# 1-Schematic_CessnaCitationX_Front.net
KiCad netlist of a schematic drawn in EasyEDA
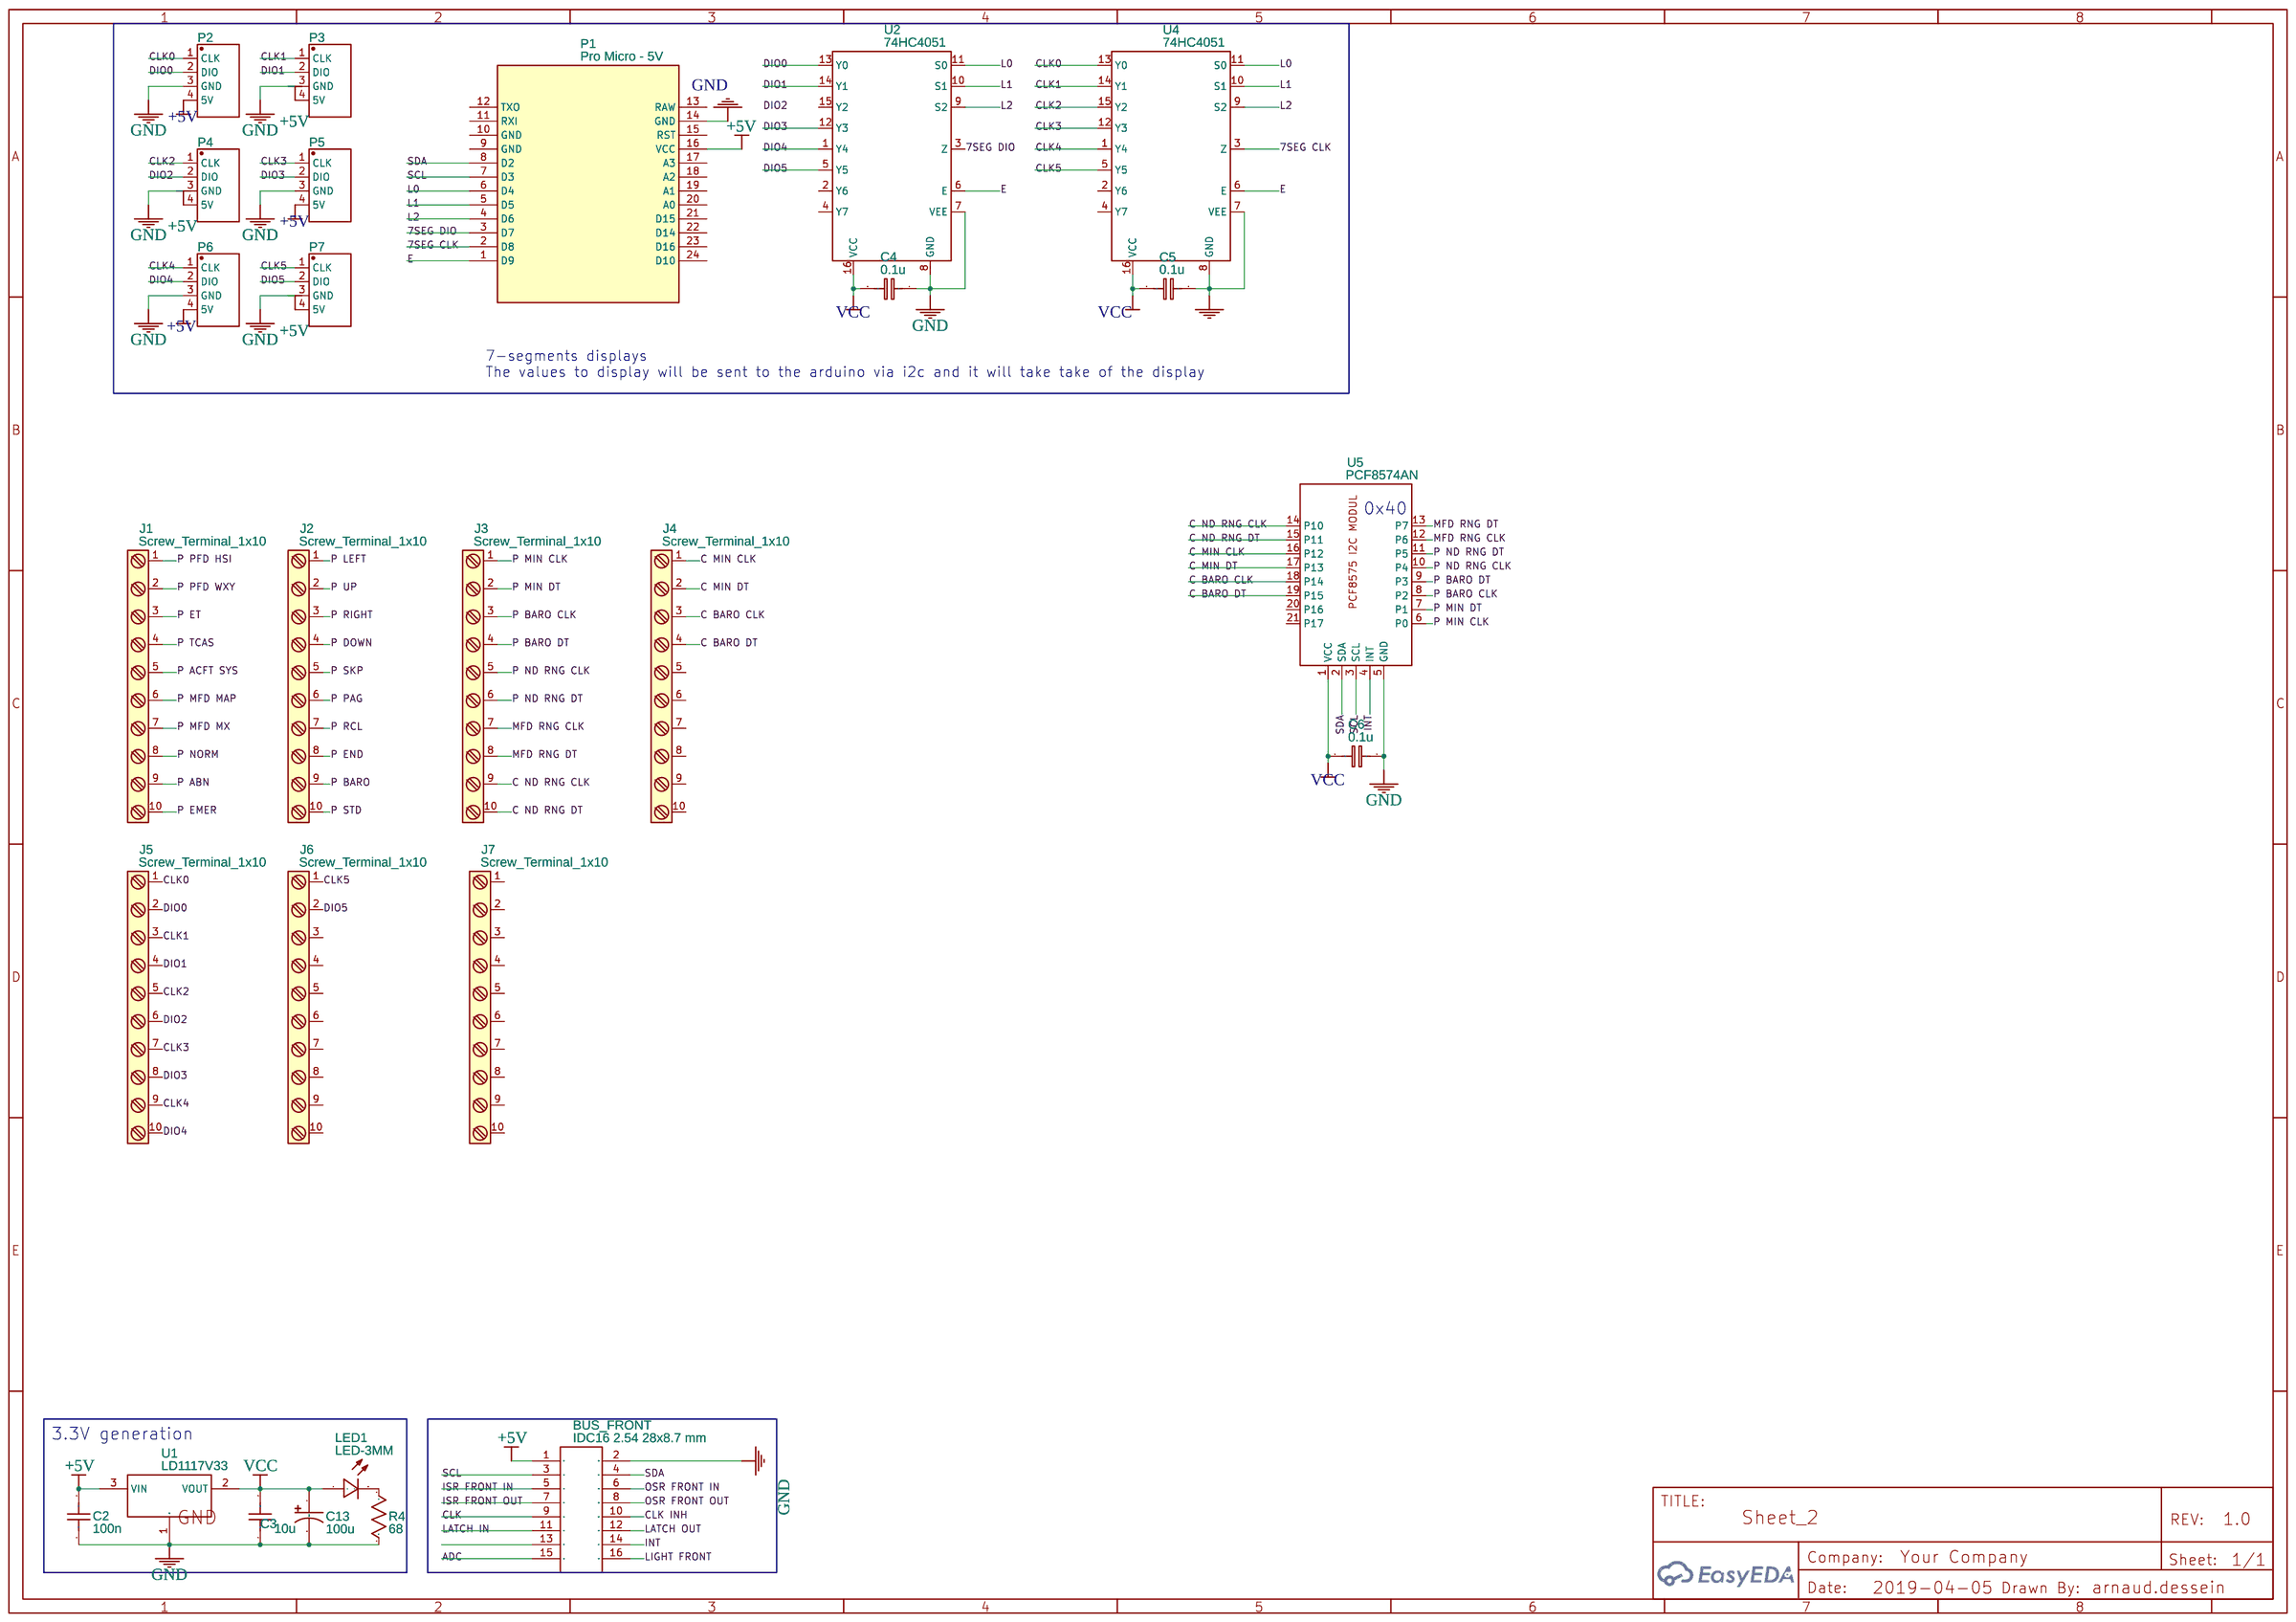
[diagram p0: schematic sheet]

(export (version "E")
  (design (tool "Eeschema 10.0.6"))
  (components
    (comp (ref "BUS_FRONT")
      (value "IDC16 2.54 28x8.7 mm")
      (fields (field (name "BOM_Manufacturer Part") "?"))
      (libsource (lib "") (part "Unknown_375_1120"))
    )
    (comp (ref "C2")
      (value "100n")
      (fields (field (name "BOM_Manufacturer Part") "?"))
      (libsource (lib "") (part "Cap_RAD-0.1_US"))
    )
    (comp (ref "C3")
      (value "10u")
      (fields (field (name "BOM_Manufacturer Part") "?"))
      (libsource (lib "") (part "Cap_RAD-0.1_US"))
    )
    (comp (ref "C4")
      (value "0.1u")
      (fields (field (name "BOM_Manufacturer Part") "?"))
      (libsource (lib "") (part "Cap_RAD-0.1_EU"))
    )
    (comp (ref "C5")
      (value "0.1u")
      (fields (field (name "BOM_Manufacturer Part") "?"))
      (libsource (lib "") (part "Cap_RAD-0.1_EU"))
    )
    (comp (ref "C6")
      (value "0.1u")
      (fields (field (name "BOM_Manufacturer Part") "?"))
      (libsource (lib "") (part "Cap_RAD-0.1_EU_1"))
    )
    (comp (ref "C13")
      (value "100u")
      (fields (field (name "BOM_Manufacturer Part") "?"))
      (libsource (lib "") (part "Cap_Electrolytic(TH)_D3.0XF1.5_US"))
    )
    (comp (ref "J1")
      (value "Screw_Terminal_1x10")
      (fields (field (name "BOM_Manufacturer Part") "?"))
      (libsource (lib "") (part "Unknown_100_395"))
    )
    (comp (ref "J2")
      (value "Screw_Terminal_1x10")
      (fields (field (name "BOM_Manufacturer Part") "?"))
      (libsource (lib "") (part "Unknown_215_395"))
    )
    (comp (ref "J3")
      (value "Screw_Terminal_1x10")
      (fields (field (name "BOM_Manufacturer Part") "?"))
      (libsource (lib "") (part "Unknown_340_395"))
    )
    (comp (ref "J4")
      (value "Screw_Terminal_1x10")
      (fields (field (name "BOM_Manufacturer Part") "?"))
      (libsource (lib "") (part "Unknown_475_395"))
    )
    (comp (ref "J5")
      (value "Screw_Terminal_1x10")
      (fields (field (name "BOM_Manufacturer Part") "?"))
      (libsource (lib "") (part "Unknown_100_625"))
    )
    (comp (ref "J6")
      (value "Screw_Terminal_1x10")
      (fields (field (name "BOM_Manufacturer Part") "?"))
      (libsource (lib "") (part "Unknown_215_625"))
    )
    (comp (ref "J7")
      (value "Screw_Terminal_1x10")
      (fields (field (name "BOM_Manufacturer Part") "?"))
      (libsource (lib "") (part "Unknown_345_625"))
    )
    (comp (ref "LED1")
      (value "LED-3MM")
      (fields
        (field (name "BOM_Manufacturer Part") "204-10SURD/S530-A3")
        (field (name "BOM_Supplier Part") "C99772")
      )
      (libsource (lib "") (part "Unknown_245_1055"))
    )
    (comp (ref "P1")
      (value "Pro Micro - 5V")
      (fields (field (name "BOM_Manufacturer Part") "?"))
      (libsource (lib "") (part "Unknown_415_125"))
    )
    (comp (ref "P2")
      (value "7seg display module TM1637")
      (fields
        (field (name "BOM_Manufacturer Part") "WJ2EDGVC-5.08-4P")
        (field (name "BOM_Supplier Part") "C8471")
      )
      (libsource (lib "") (part "Unknown_140_50"))
    )
    (comp (ref "P3")
      (value "7seg display module TM1637")
      (fields
        (field (name "BOM_Manufacturer Part") "WJ2EDGVC-5.08-4P")
        (field (name "BOM_Supplier Part") "C8471")
      )
      (libsource (lib "") (part "Unknown_220_50"))
    )
    (comp (ref "P4")
      (value "7seg display module TM1637")
      (fields
        (field (name "BOM_Manufacturer Part") "WJ2EDGVC-5.08-4P")
        (field (name "BOM_Supplier Part") "C8471")
      )
      (libsource (lib "") (part "Unknown_140_125"))
    )
    (comp (ref "P5")
      (value "7seg display module TM1637")
      (fields
        (field (name "BOM_Manufacturer Part") "WJ2EDGVC-5.08-4P")
        (field (name "BOM_Supplier Part") "C8471")
      )
      (libsource (lib "") (part "Unknown_220_125"))
    )
    (comp (ref "P6")
      (value "7seg display module TM1637")
      (fields
        (field (name "BOM_Manufacturer Part") "WJ2EDGVC-5.08-4P")
        (field (name "BOM_Supplier Part") "C8471")
      )
      (libsource (lib "") (part "Unknown_140_200"))
    )
    (comp (ref "P7")
      (value "7seg display module TM1637")
      (fields
        (field (name "BOM_Manufacturer Part") "WJ2EDGVC-5.08-4P")
        (field (name "BOM_Supplier Part") "C8471")
      )
      (libsource (lib "") (part "Unknown_220_200"))
    )
    (comp (ref "R4")
      (value "68")
      (fields (field (name "BOM_Manufacturer Part") "?"))
      (libsource (lib "") (part "Res_AXIAL-0.3(1/8W)_US"))
    )
    (comp (ref "U1")
      (value "LD1117V33")
      (fields (field (name "BOM_Supplier Part") "C283467"))
      (libsource (lib "") (part "Unknown_115_1080"))
    )
    (comp (ref "U2")
      (value "74HC4051")
      (fields (field (name "BOM_Manufacturer Part") "?"))
      (libsource (lib "") (part "Unknown_635_100"))
    )
    (comp (ref "U4")
      (value "74HC4051")
      (fields (field (name "BOM_Manufacturer Part") "?"))
      (libsource (lib "") (part "Unknown_835_100"))
    )
    (comp (ref "U5")
      (value "PCF8574AN")
      (fields (field (name "BOM_Manufacturer Part") "?"))
      (libsource (lib "") (part "Unknown_905_350"))
    )
  )
  (nets
    (net (code "1") (name "+5V") (class "Default")
      (node (ref "BUS_FRONT") (pin "1") (pinfunction "P1_1") (pintype "unspecified"))
      (node (ref "C2") (pin "2") (pinfunction "2_2") (pintype "unspecified"))
      (node (ref "P1") (pin "16") (pinfunction "VCC_16") (pintype "unspecified"))
      (node (ref "P2") (pin "4") (pinfunction "5V_4") (pintype "unspecified"))
      (node (ref "P3") (pin "4") (pinfunction "5V_4") (pintype "unspecified"))
      (node (ref "P4") (pin "4") (pinfunction "5V_4") (pintype "unspecified"))
      (node (ref "P5") (pin "4") (pinfunction "5V_4") (pintype "unspecified"))
      (node (ref "P6") (pin "4") (pinfunction "5V_4") (pintype "unspecified"))
      (node (ref "P7") (pin "4") (pinfunction "5V_4") (pintype "unspecified"))
      (node (ref "U1") (pin "3") (pinfunction "VIN_3") (pintype "passive"))
    )
    (net (code "2") (name "/7SEG CLK") (class "Default")
      (node (ref "P1") (pin "2") (pinfunction "D8_2") (pintype "unspecified"))
      (node (ref "U4") (pin "3") (pinfunction "Z_3") (pintype "unspecified"))
    )
    (net (code "3") (name "/7SEG DIO") (class "Default")
      (node (ref "P1") (pin "3") (pinfunction "D7_3") (pintype "unspecified"))
      (node (ref "U2") (pin "3") (pinfunction "Z_3") (pintype "unspecified"))
    )
    (net (code "4") (name "/ADC") (class "Default")
      (node (ref "BUS_FRONT") (pin "15") (pinfunction "15_15") (pintype "unspecified"))
    )
    (net (code "5") (name "/C BARO CLK") (class "Default")
      (node (ref "J4") (pin "3") (pintype "unspecified"))
      (node (ref "U5") (pin "18") (pinfunction "P14_18") (pintype "unspecified"))
    )
    (net (code "6") (name "/C BARO DT") (class "Default")
      (node (ref "J4") (pin "4") (pintype "unspecified"))
      (node (ref "U5") (pin "19") (pinfunction "P15_19") (pintype "unspecified"))
    )
    (net (code "7") (name "/C MIN CLK") (class "Default")
      (node (ref "J4") (pin "1") (pintype "unspecified"))
      (node (ref "U5") (pin "16") (pinfunction "P12_16") (pintype "unspecified"))
    )
    (net (code "8") (name "/C MIN DT") (class "Default")
      (node (ref "J4") (pin "2") (pintype "unspecified"))
      (node (ref "U5") (pin "17") (pinfunction "P13_17") (pintype "unspecified"))
    )
    (net (code "9") (name "/C ND RNG CLK") (class "Default")
      (node (ref "J3") (pin "9") (pintype "unspecified"))
      (node (ref "U5") (pin "14") (pinfunction "P10_14") (pintype "unspecified"))
    )
    (net (code "10") (name "/C ND RNG DT") (class "Default")
      (node (ref "J3") (pin "10") (pintype "unspecified"))
      (node (ref "U5") (pin "15") (pinfunction "P11_15") (pintype "unspecified"))
    )
    (net (code "11") (name "/CLK") (class "Default")
      (node (ref "BUS_FRONT") (pin "9") (pinfunction "P9_9") (pintype "unspecified"))
    )
    (net (code "12") (name "/CLK INH") (class "Default")
      (node (ref "BUS_FRONT") (pin "10") (pinfunction "P10_10") (pintype "unspecified"))
    )
    (net (code "13") (name "/CLK0") (class "Default")
      (node (ref "J5") (pin "1") (pintype "unspecified"))
      (node (ref "P2") (pin "1") (pinfunction "CLK_1") (pintype "unspecified"))
      (node (ref "U4") (pin "13") (pinfunction "Y0_13") (pintype "unspecified"))
    )
    (net (code "14") (name "/CLK1") (class "Default")
      (node (ref "J5") (pin "3") (pintype "unspecified"))
      (node (ref "P3") (pin "1") (pinfunction "CLK_1") (pintype "unspecified"))
      (node (ref "U4") (pin "14") (pinfunction "Y1_14") (pintype "unspecified"))
    )
    (net (code "15") (name "/CLK2") (class "Default")
      (node (ref "J5") (pin "5") (pintype "unspecified"))
      (node (ref "P4") (pin "1") (pinfunction "CLK_1") (pintype "unspecified"))
      (node (ref "U4") (pin "15") (pinfunction "Y2_15") (pintype "unspecified"))
    )
    (net (code "16") (name "/CLK3") (class "Default")
      (node (ref "J5") (pin "7") (pintype "unspecified"))
      (node (ref "P5") (pin "1") (pinfunction "CLK_1") (pintype "unspecified"))
      (node (ref "U4") (pin "12") (pinfunction "Y3_12") (pintype "unspecified"))
    )
    (net (code "17") (name "/CLK4") (class "Default")
      (node (ref "J5") (pin "9") (pintype "unspecified"))
      (node (ref "P6") (pin "1") (pinfunction "CLK_1") (pintype "unspecified"))
      (node (ref "U4") (pin "1") (pinfunction "Y4_1") (pintype "unspecified"))
    )
    (net (code "18") (name "/CLK5") (class "Default")
      (node (ref "J6") (pin "1") (pintype "unspecified"))
      (node (ref "P7") (pin "1") (pinfunction "CLK_1") (pintype "unspecified"))
      (node (ref "U4") (pin "5") (pinfunction "Y5_5") (pintype "unspecified"))
    )
    (net (code "19") (name "/DIO0") (class "Default")
      (node (ref "J5") (pin "2") (pintype "unspecified"))
      (node (ref "P2") (pin "2") (pinfunction "DIO_2") (pintype "unspecified"))
      (node (ref "U2") (pin "13") (pinfunction "Y0_13") (pintype "unspecified"))
    )
    (net (code "20") (name "/DIO1") (class "Default")
      (node (ref "J5") (pin "4") (pintype "unspecified"))
      (node (ref "P3") (pin "2") (pinfunction "DIO_2") (pintype "unspecified"))
      (node (ref "U2") (pin "14") (pinfunction "Y1_14") (pintype "unspecified"))
    )
    (net (code "21") (name "/DIO2") (class "Default")
      (node (ref "J5") (pin "6") (pintype "unspecified"))
      (node (ref "P4") (pin "2") (pinfunction "DIO_2") (pintype "unspecified"))
    )
    (net (code "22") (name "/DIO3") (class "Default")
      (node (ref "J5") (pin "8") (pintype "unspecified"))
      (node (ref "P5") (pin "2") (pinfunction "DIO_2") (pintype "unspecified"))
      (node (ref "U2") (pin "12") (pinfunction "Y3_12") (pintype "unspecified"))
    )
    (net (code "23") (name "/DIO4") (class "Default")
      (node (ref "J5") (pin "10") (pintype "unspecified"))
      (node (ref "P6") (pin "2") (pinfunction "DIO_2") (pintype "unspecified"))
      (node (ref "U2") (pin "1") (pinfunction "Y4_1") (pintype "unspecified"))
    )
    (net (code "24") (name "/DIO5") (class "Default")
      (node (ref "J6") (pin "2") (pintype "unspecified"))
      (node (ref "P7") (pin "2") (pinfunction "DIO_2") (pintype "unspecified"))
      (node (ref "U2") (pin "5") (pinfunction "Y5_5") (pintype "unspecified"))
    )
    (net (code "25") (name "/E") (class "Default")
      (node (ref "P1") (pin "1") (pinfunction "D9_1") (pintype "unspecified"))
      (node (ref "U2") (pin "6") (pinfunction "E_6") (pintype "unspecified"))
      (node (ref "U4") (pin "6") (pinfunction "E_6") (pintype "unspecified"))
    )
    (net (code "26") (name "/INT") (class "Default")
      (node (ref "BUS_FRONT") (pin "14") (pinfunction "14_14") (pintype "unspecified"))
      (node (ref "U5") (pin "4") (pinfunction "INT_4") (pintype "unspecified"))
    )
    (net (code "27") (name "/ISR FRONT IN") (class "Default")
      (node (ref "BUS_FRONT") (pin "5") (pinfunction "P5_5") (pintype "unspecified"))
    )
    (net (code "28") (name "/ISR FRONT OUT") (class "Default")
      (node (ref "BUS_FRONT") (pin "7") (pinfunction "P7_7") (pintype "unspecified"))
    )
    (net (code "29") (name "/L0") (class "Default")
      (node (ref "P1") (pin "6") (pinfunction "D4_6") (pintype "unspecified"))
      (node (ref "U2") (pin "11") (pinfunction "S0_11") (pintype "unspecified"))
      (node (ref "U4") (pin "11") (pinfunction "S0_11") (pintype "unspecified"))
    )
    (net (code "30") (name "/L1") (class "Default")
      (node (ref "P1") (pin "5") (pinfunction "D5_5") (pintype "unspecified"))
      (node (ref "U2") (pin "10") (pinfunction "S1_10") (pintype "unspecified"))
      (node (ref "U4") (pin "10") (pinfunction "S1_10") (pintype "unspecified"))
    )
    (net (code "31") (name "/L2") (class "Default")
      (node (ref "P1") (pin "4") (pinfunction "D6_4") (pintype "unspecified"))
      (node (ref "U2") (pin "9") (pinfunction "S2_9") (pintype "unspecified"))
      (node (ref "U4") (pin "9") (pinfunction "S2_9") (pintype "unspecified"))
    )
    (net (code "32") (name "/LATCH IN") (class "Default")
      (node (ref "BUS_FRONT") (pin "11") (pinfunction "11_11") (pintype "unspecified"))
    )
    (net (code "33") (name "/LATCH OUT") (class "Default")
      (node (ref "BUS_FRONT") (pin "12") (pinfunction "12_12") (pintype "unspecified"))
    )
    (net (code "34") (name "/LIGHT FRONT") (class "Default")
      (node (ref "BUS_FRONT") (pin "16") (pinfunction "16_16") (pintype "unspecified"))
    )
    (net (code "35") (name "/MFD RNG CLK") (class "Default")
      (node (ref "J3") (pin "7") (pintype "unspecified"))
      (node (ref "U5") (pin "12") (pinfunction "P6_12") (pintype "unspecified"))
    )
    (net (code "36") (name "/MFD RNG DT") (class "Default")
      (node (ref "J3") (pin "8") (pintype "unspecified"))
      (node (ref "U5") (pin "13") (pinfunction "P7_13") (pintype "unspecified"))
    )
    (net (code "37") (name "/OSR FRONT IN") (class "Default")
      (node (ref "BUS_FRONT") (pin "6") (pinfunction "P6_6") (pintype "unspecified"))
    )
    (net (code "38") (name "/OSR FRONT OUT") (class "Default")
      (node (ref "BUS_FRONT") (pin "8") (pinfunction "P8_8") (pintype "unspecified"))
    )
    (net (code "39") (name "/P ABN") (class "Default") (node (ref "J1") (pin "9") (pintype "unspecified")))
    (net (code "40") (name "/P ACFT SYS") (class "Default")
      (node (ref "J1") (pin "5") (pintype "unspecified"))
    )
    (net (code "41") (name "/P BARO") (class "Default") (node (ref "J2") (pin "9") (pintype "unspecified")))
    (net (code "42") (name "/P BARO CLK") (class "Default")
      (node (ref "J3") (pin "3") (pintype "unspecified"))
      (node (ref "U5") (pin "8") (pinfunction "P2_8") (pintype "unspecified"))
    )
    (net (code "43") (name "/P BARO DT") (class "Default")
      (node (ref "J3") (pin "4") (pintype "unspecified"))
      (node (ref "U5") (pin "9") (pinfunction "P3_9") (pintype "unspecified"))
    )
    (net (code "44") (name "/P DOWN") (class "Default") (node (ref "J2") (pin "4") (pintype "unspecified")))
    (net (code "45") (name "/P EMER") (class "Default") (node (ref "J1") (pin "10") (pintype "unspecified")))
    (net (code "46") (name "/P END") (class "Default") (node (ref "J2") (pin "8") (pintype "unspecified")))
    (net (code "47") (name "/P ET") (class "Default") (node (ref "J1") (pin "3") (pintype "unspecified")))
    (net (code "48") (name "/P LEFT") (class "Default") (node (ref "J2") (pin "1") (pintype "unspecified")))
    (net (code "49") (name "/P MFD MAP") (class "Default")
      (node (ref "J1") (pin "6") (pintype "unspecified"))
    )
    (net (code "50") (name "/P MFD MX") (class "Default") (node (ref "J1") (pin "7") (pintype "unspecified")))
    (net (code "51") (name "/P MIN CLK") (class "Default")
      (node (ref "J3") (pin "1") (pintype "unspecified"))
      (node (ref "U5") (pin "6") (pinfunction "P0_6") (pintype "unspecified"))
    )
    (net (code "52") (name "/P MIN DT") (class "Default")
      (node (ref "J3") (pin "2") (pintype "unspecified"))
      (node (ref "U5") (pin "7") (pinfunction "P1_7") (pintype "unspecified"))
    )
    (net (code "53") (name "/P ND RNG CLK") (class "Default")
      (node (ref "J3") (pin "5") (pintype "unspecified"))
      (node (ref "U5") (pin "10") (pinfunction "P4_10") (pintype "unspecified"))
    )
    (net (code "54") (name "/P ND RNG DT") (class "Default")
      (node (ref "J3") (pin "6") (pintype "unspecified"))
      (node (ref "U5") (pin "11") (pinfunction "P5_11") (pintype "unspecified"))
    )
    (net (code "55") (name "/P NORM") (class "Default") (node (ref "J1") (pin "8") (pintype "unspecified")))
    (net (code "56") (name "/P PAG") (class "Default") (node (ref "J2") (pin "6") (pintype "unspecified")))
    (net (code "57") (name "/P PFD HSI") (class "Default")
      (node (ref "J1") (pin "1") (pintype "unspecified"))
    )
    (net (code "58") (name "/P PFD WXY") (class "Default")
      (node (ref "J1") (pin "2") (pintype "unspecified"))
    )
    (net (code "59") (name "/P RCL") (class "Default") (node (ref "J2") (pin "7") (pintype "unspecified")))
    (net (code "60") (name "/P RIGHT") (class "Default") (node (ref "J2") (pin "3") (pintype "unspecified")))
    (net (code "61") (name "/P SKP") (class "Default") (node (ref "J2") (pin "5") (pintype "unspecified")))
    (net (code "62") (name "/P STD") (class "Default") (node (ref "J2") (pin "10") (pintype "unspecified")))
    (net (code "63") (name "/P TCAS") (class "Default") (node (ref "J1") (pin "4") (pintype "unspecified")))
    (net (code "64") (name "/P UP") (class "Default") (node (ref "J2") (pin "2") (pintype "unspecified")))
    (net (code "65") (name "/SCL") (class "Default")
      (node (ref "BUS_FRONT") (pin "3") (pinfunction "P3_3") (pintype "unspecified"))
      (node (ref "P1") (pin "7") (pinfunction "D3_7") (pintype "unspecified"))
      (node (ref "U5") (pin "3") (pinfunction "SCL_3") (pintype "unspecified"))
    )
    (net (code "66") (name "/SDA") (class "Default")
      (node (ref "BUS_FRONT") (pin "4") (pinfunction "P4_4") (pintype "unspecified"))
      (node (ref "P1") (pin "8") (pinfunction "D2_8") (pintype "unspecified"))
      (node (ref "U5") (pin "2") (pinfunction "SDA_2") (pintype "unspecified"))
    )
    (net (code "67") (name "GND") (class "Default")
      (node (ref "BUS_FRONT") (pin "2") (pinfunction "P2_2") (pintype "unspecified"))
      (node (ref "C13") (pin "2") (pinfunction "2_2") (pintype "unspecified"))
      (node (ref "C2") (pin "1") (pinfunction "1_1") (pintype "unspecified"))
      (node (ref "C3") (pin "1") (pinfunction "1_1") (pintype "unspecified"))
      (node (ref "C4") (pin "1") (pinfunction "1_1") (pintype "unspecified"))
      (node (ref "C5") (pin "1") (pinfunction "1_1") (pintype "unspecified"))
      (node (ref "C6") (pin "1") (pinfunction "1_1") (pintype "unspecified"))
      (node (ref "P1") (pin "14") (pinfunction "GND_14") (pintype "unspecified"))
      (node (ref "P2") (pin "3") (pinfunction "GND_3") (pintype "unspecified"))
      (node (ref "P3") (pin "3") (pinfunction "GND_3") (pintype "unspecified"))
      (node (ref "P4") (pin "3") (pinfunction "GND_3") (pintype "unspecified"))
      (node (ref "P5") (pin "3") (pinfunction "GND_3") (pintype "unspecified"))
      (node (ref "P6") (pin "3") (pinfunction "GND_3") (pintype "unspecified"))
      (node (ref "P7") (pin "3") (pinfunction "GND_3") (pintype "unspecified"))
      (node (ref "R4") (pin "2") (pinfunction "2_2") (pintype "unspecified"))
      (node (ref "U1") (pin "1") (pinfunction "GND_1") (pintype "unspecified"))
      (node (ref "U2") (pin "7") (pinfunction "VEE_7") (pintype "unspecified"))
      (node (ref "U2") (pin "8") (pinfunction "GND_8") (pintype "unspecified"))
      (node (ref "U4") (pin "7") (pinfunction "VEE_7") (pintype "unspecified"))
      (node (ref "U4") (pin "8") (pinfunction "GND_8") (pintype "unspecified"))
      (node (ref "U5") (pin "5") (pinfunction "GND_5") (pintype "unspecified"))
    )
    (net (code "68") (name "Net-(LED1--)") (class "Default")
      (node (ref "LED1") (pin "2") (pinfunction "-_2") (pintype "unspecified"))
      (node (ref "R4") (pin "1") (pinfunction "1_1") (pintype "unspecified"))
    )
    (net (code "69") (name "VCC") (class "Default")
      (node (ref "C13") (pin "1") (pinfunction "1_1") (pintype "unspecified"))
      (node (ref "C3") (pin "2") (pinfunction "2_2") (pintype "unspecified"))
      (node (ref "C4") (pin "2") (pinfunction "2_2") (pintype "unspecified"))
      (node (ref "C5") (pin "2") (pinfunction "2_2") (pintype "unspecified"))
      (node (ref "C6") (pin "2") (pinfunction "2_2") (pintype "unspecified"))
      (node (ref "LED1") (pin "1") (pinfunction "+_1") (pintype "unspecified"))
      (node (ref "U1") (pin "2") (pinfunction "VOUT_2") (pintype "passive"))
      (node (ref "U2") (pin "16") (pinfunction "VCC_16") (pintype "unspecified"))
      (node (ref "U4") (pin "16") (pinfunction "VCC_16") (pintype "unspecified"))
      (node (ref "U5") (pin "1") (pinfunction "VCC_1") (pintype "unspecified"))
    )
    (net (code "70") (name "unconnected-(BUS_FRONT-Pad13)") (class "Default")
      (node (ref "BUS_FRONT") (pin "13") (pinfunction "13_13") (pintype "unspecified"))
    )
    (net (code "71") (name "unconnected-(J4-Pad5)") (class "Default")
      (node (ref "J4") (pin "5") (pintype "unspecified"))
    )
    (net (code "72") (name "unconnected-(J4-Pad6)") (class "Default")
      (node (ref "J4") (pin "6") (pintype "unspecified"))
    )
    (net (code "73") (name "unconnected-(J4-Pad7)") (class "Default")
      (node (ref "J4") (pin "7") (pintype "unspecified"))
    )
    (net (code "74") (name "unconnected-(J4-Pad8)") (class "Default")
      (node (ref "J4") (pin "8") (pintype "unspecified"))
    )
    (net (code "75") (name "unconnected-(J4-Pad9)") (class "Default")
      (node (ref "J4") (pin "9") (pintype "unspecified"))
    )
    (net (code "76") (name "unconnected-(J4-Pad10)") (class "Default")
      (node (ref "J4") (pin "10") (pintype "unspecified"))
    )
    (net (code "77") (name "unconnected-(J6-Pad3)") (class "Default")
      (node (ref "J6") (pin "3") (pintype "unspecified"))
    )
    (net (code "78") (name "unconnected-(J6-Pad4)") (class "Default")
      (node (ref "J6") (pin "4") (pintype "unspecified"))
    )
    (net (code "79") (name "unconnected-(J6-Pad5)") (class "Default")
      (node (ref "J6") (pin "5") (pintype "unspecified"))
    )
    (net (code "80") (name "unconnected-(J6-Pad6)") (class "Default")
      (node (ref "J6") (pin "6") (pintype "unspecified"))
    )
    (net (code "81") (name "unconnected-(J6-Pad7)") (class "Default")
      (node (ref "J6") (pin "7") (pintype "unspecified"))
    )
    (net (code "82") (name "unconnected-(J6-Pad8)") (class "Default")
      (node (ref "J6") (pin "8") (pintype "unspecified"))
    )
    (net (code "83") (name "unconnected-(J6-Pad9)") (class "Default")
      (node (ref "J6") (pin "9") (pintype "unspecified"))
    )
    (net (code "84") (name "unconnected-(J6-Pad10)") (class "Default")
      (node (ref "J6") (pin "10") (pintype "unspecified"))
    )
    (net (code "85") (name "unconnected-(J7-Pad1)") (class "Default")
      (node (ref "J7") (pin "1") (pintype "unspecified"))
    )
    (net (code "86") (name "unconnected-(J7-Pad2)") (class "Default")
      (node (ref "J7") (pin "2") (pintype "unspecified"))
    )
    (net (code "87") (name "unconnected-(J7-Pad3)") (class "Default")
      (node (ref "J7") (pin "3") (pintype "unspecified"))
    )
    (net (code "88") (name "unconnected-(J7-Pad4)") (class "Default")
      (node (ref "J7") (pin "4") (pintype "unspecified"))
    )
    (net (code "89") (name "unconnected-(J7-Pad5)") (class "Default")
      (node (ref "J7") (pin "5") (pintype "unspecified"))
    )
    (net (code "90") (name "unconnected-(J7-Pad6)") (class "Default")
      (node (ref "J7") (pin "6") (pintype "unspecified"))
    )
    (net (code "91") (name "unconnected-(J7-Pad7)") (class "Default")
      (node (ref "J7") (pin "7") (pintype "unspecified"))
    )
    (net (code "92") (name "unconnected-(J7-Pad8)") (class "Default")
      (node (ref "J7") (pin "8") (pintype "unspecified"))
    )
    (net (code "93") (name "unconnected-(J7-Pad9)") (class "Default")
      (node (ref "J7") (pin "9") (pintype "unspecified"))
    )
    (net (code "94") (name "unconnected-(J7-Pad10)") (class "Default")
      (node (ref "J7") (pin "10") (pintype "unspecified"))
    )
    (net (code "95") (name "unconnected-(P1-A0-Pad20)") (class "Default")
      (node (ref "P1") (pin "20") (pinfunction "A0_20") (pintype "unspecified"))
    )
    (net (code "96") (name "unconnected-(P1-A1-Pad19)") (class "Default")
      (node (ref "P1") (pin "19") (pinfunction "A1_19") (pintype "unspecified"))
    )
    (net (code "97") (name "unconnected-(P1-A2-Pad18)") (class "Default")
      (node (ref "P1") (pin "18") (pinfunction "A2_18") (pintype "unspecified"))
    )
    (net (code "98") (name "unconnected-(P1-A3-Pad17)") (class "Default")
      (node (ref "P1") (pin "17") (pinfunction "A3_17") (pintype "unspecified"))
    )
    (net (code "99") (name "unconnected-(P1-D10-Pad24)") (class "Default")
      (node (ref "P1") (pin "24") (pinfunction "D10_24") (pintype "unspecified"))
    )
    (net (code "100") (name "unconnected-(P1-D14-Pad22)") (class "Default")
      (node (ref "P1") (pin "22") (pinfunction "D14_22") (pintype "unspecified"))
    )
    (net (code "101") (name "unconnected-(P1-D15-Pad21)") (class "Default")
      (node (ref "P1") (pin "21") (pinfunction "D15_21") (pintype "unspecified"))
    )
    (net (code "102") (name "unconnected-(P1-D16-Pad23)") (class "Default")
      (node (ref "P1") (pin "23") (pinfunction "D16_23") (pintype "unspecified"))
    )
    (net (code "103") (name "unconnected-(P1-GND-Pad9)") (class "Default")
      (node (ref "P1") (pin "9") (pinfunction "GND_9") (pintype "unspecified"))
    )
    (net (code "104") (name "unconnected-(P1-GND-Pad10)") (class "Default")
      (node (ref "P1") (pin "10") (pinfunction "GND_10") (pintype "unspecified"))
    )
    (net (code "105") (name "unconnected-(P1-RAW-Pad13)") (class "Default")
      (node (ref "P1") (pin "13") (pinfunction "RAW_13") (pintype "unspecified"))
    )
    (net (code "106") (name "unconnected-(P1-RST-Pad15)") (class "Default")
      (node (ref "P1") (pin "15") (pinfunction "RST_15") (pintype "unspecified"))
    )
    (net (code "107") (name "unconnected-(P1-RXI-Pad11)") (class "Default")
      (node (ref "P1") (pin "11") (pinfunction "RXI_11") (pintype "unspecified"))
    )
    (net (code "108") (name "unconnected-(P1-TXO-Pad12)") (class "Default")
      (node (ref "P1") (pin "12") (pinfunction "TXO_12") (pintype "unspecified"))
    )
    (net (code "109") (name "unconnected-(U2-Y2-Pad15)") (class "Default")
      (node (ref "U2") (pin "15") (pinfunction "Y2_15") (pintype "unspecified"))
    )
    (net (code "110") (name "unconnected-(U2-Y6-Pad2)") (class "Default")
      (node (ref "U2") (pin "2") (pinfunction "Y6_2") (pintype "unspecified"))
    )
    (net (code "111") (name "unconnected-(U2-Y7-Pad4)") (class "Default")
      (node (ref "U2") (pin "4") (pinfunction "Y7_4") (pintype "unspecified"))
    )
    (net (code "112") (name "unconnected-(U4-Y6-Pad2)") (class "Default")
      (node (ref "U4") (pin "2") (pinfunction "Y6_2") (pintype "unspecified"))
    )
    (net (code "113") (name "unconnected-(U4-Y7-Pad4)") (class "Default")
      (node (ref "U4") (pin "4") (pinfunction "Y7_4") (pintype "unspecified"))
    )
    (net (code "114") (name "unconnected-(U5-P16-Pad20)") (class "Default")
      (node (ref "U5") (pin "20") (pinfunction "P16_20") (pintype "unspecified"))
    )
    (net (code "115") (name "unconnected-(U5-P17-Pad21)") (class "Default")
      (node (ref "U5") (pin "21") (pinfunction "P17_21") (pintype "unspecified"))
    )
  )
)
